# Single_Supply_Logic_Level_Converter.net
KiCad netlist of a schematic drawn in EAGLE
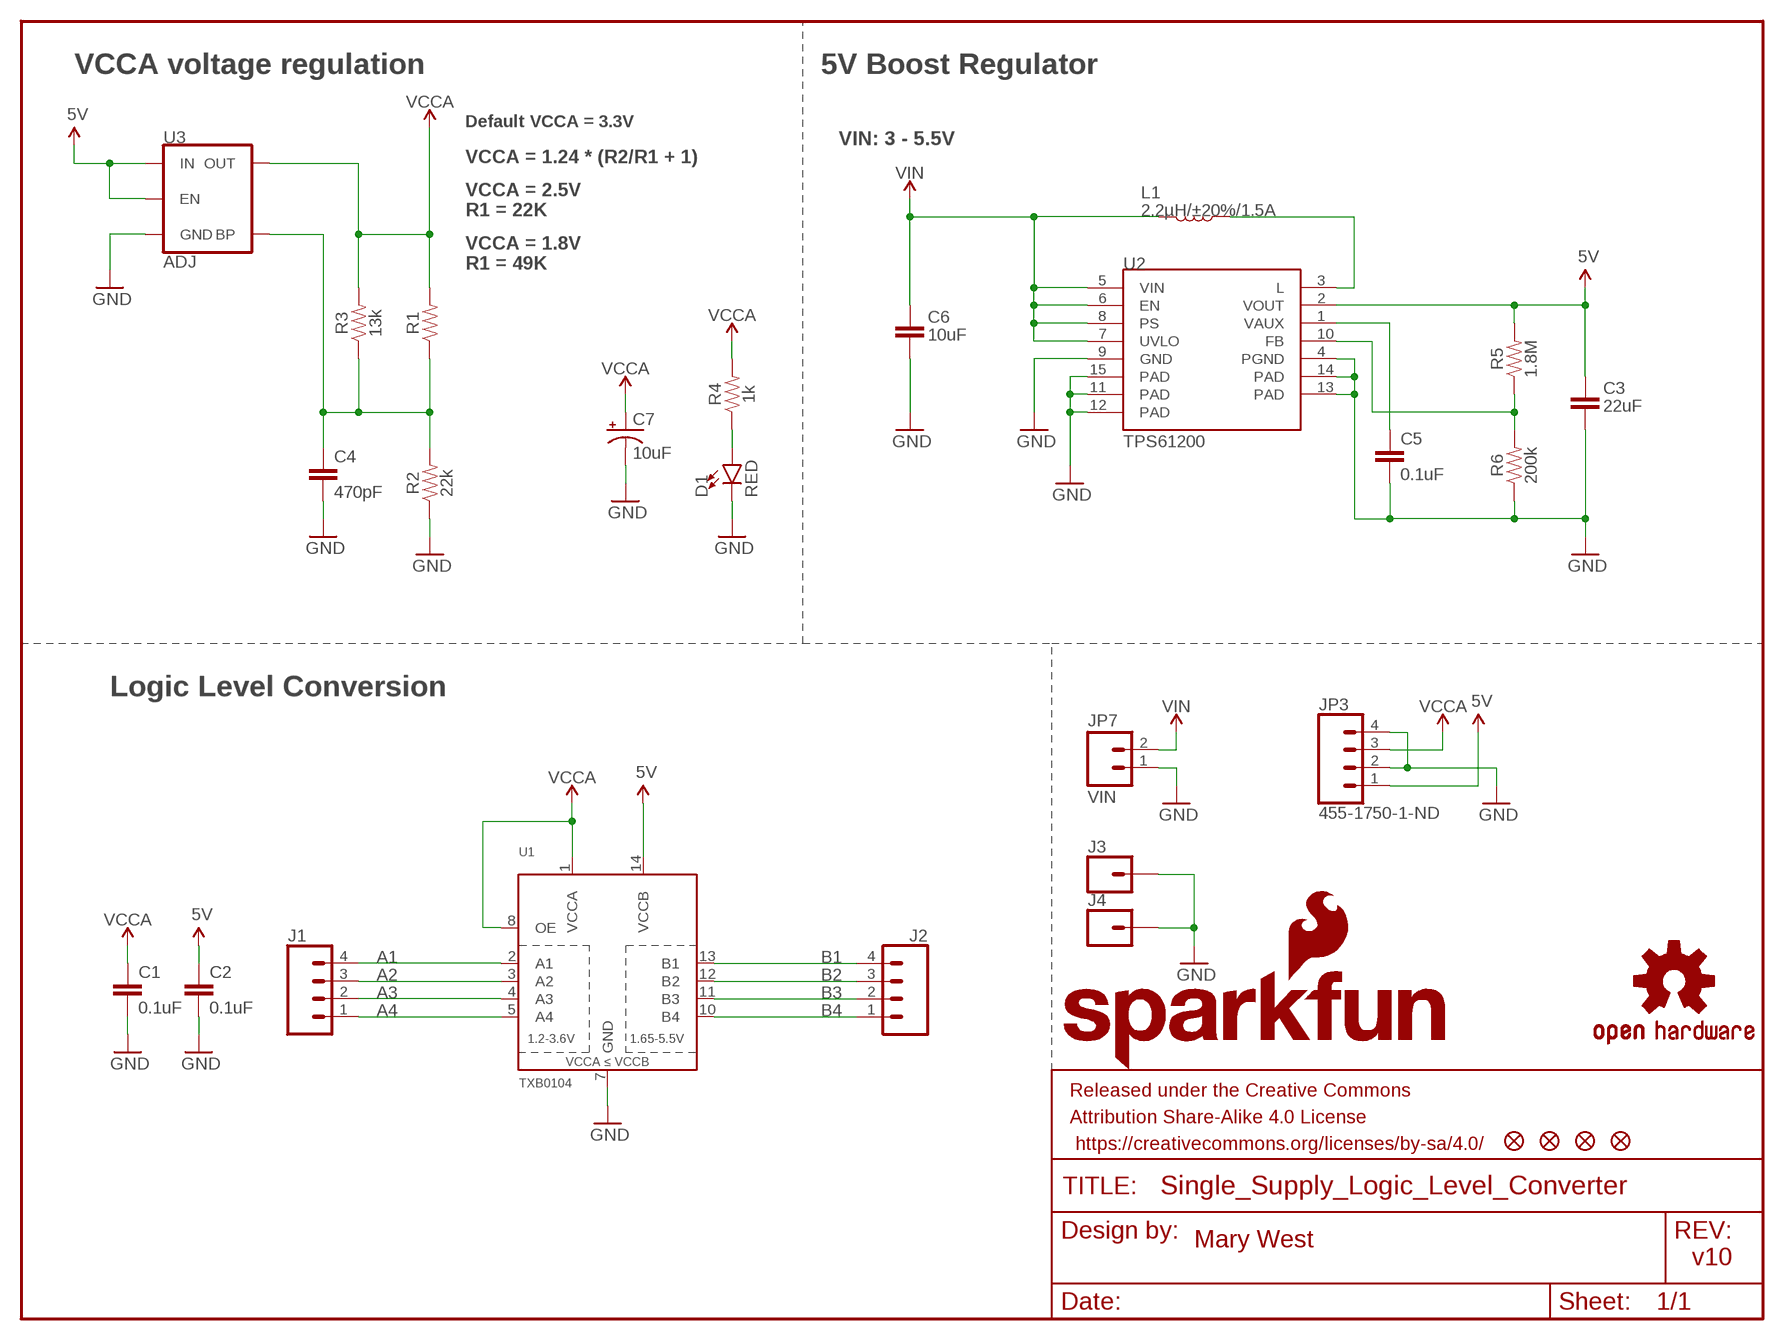
[diagram p0: schematic, sheet 1]

(export (version "E")
  (design (tool "Eeschema 10.0.6"))
  (components
    (comp (ref "C1")
      (value "0.1uF")
      (footprint "eagle-import:0603-CAP")
      (libsource (lib "eagle-import") (part "0.1UF-25V(+80/-20%)(0603)"))
    )
    (comp (ref "C2")
      (value "0.1uF")
      (footprint "eagle-import:0603-CAP")
      (libsource (lib "eagle-import") (part "0.1UF-25V(+80/-20%)(0603)"))
    )
    (comp (ref "C3")
      (value "22uF")
      (footprint "eagle-import:0805")
      (libsource (lib "eagle-import") (part "22UF-0805-6.3V-20%"))
    )
    (comp (ref "C4")
      (value "470pF")
      (footprint "eagle-import:0603")
      (libsource (lib "eagle-import") (part "470PF-0603-50V-5%"))
    )
    (comp (ref "C5")
      (value "0.1uF")
      (footprint "eagle-import:0603")
      (libsource (lib "eagle-import") (part "0.1UF-0603-25V-(+80/-20%)"))
    )
    (comp (ref "C6")
      (value "10uF")
      (footprint "eagle-import:0603")
      (libsource (lib "eagle-import") (part "10UF-0603-6.3V-20%"))
    )
    (comp (ref "C7")
      (value "10uF")
      (footprint "eagle-import:EIA3216")
      (libsource (lib "eagle-import") (part "10UF-POLAR-EIA3216-16V-10%(TANT)"))
    )
    (comp (ref "D1")
      (value "RED")
      (footprint "eagle-import:LED-0603")
      (libsource (lib "eagle-import") (part "LED-RED0603"))
    )
    (comp (ref "FD1")
      (value "FIDUCIALUFIDUCIAL")
      (footprint "eagle-import:FIDUCIAL-MICRO")
      (libsource (lib "eagle-import") (part "FIDUCIALUFIDUCIAL"))
    )
    (comp (ref "FD2")
      (value "FIDUCIALUFIDUCIAL")
      (footprint "eagle-import:FIDUCIAL-MICRO")
      (libsource (lib "eagle-import") (part "FIDUCIALUFIDUCIAL"))
    )
    (comp (ref "FD3")
      (value "FIDUCIALUFIDUCIAL")
      (footprint "eagle-import:FIDUCIAL-MICRO")
      (libsource (lib "eagle-import") (part "FIDUCIALUFIDUCIAL"))
    )
    (comp (ref "FD4")
      (value "FIDUCIALUFIDUCIAL")
      (footprint "eagle-import:FIDUCIAL-MICRO")
      (libsource (lib "eagle-import") (part "FIDUCIALUFIDUCIAL"))
    )
    (comp (ref "FRAME1")
      (value "FRAME-LETTER")
      (footprint "eagle-import:CREATIVE_COMMONS")
      (libsource (lib "eagle-import") (part "FRAME-LETTER"))
    )
    (comp (ref "J1")
      (value "CONN_04")
      (footprint "eagle-import:1X04")
      (libsource (lib "eagle-import") (part "CONN_04"))
    )
    (comp (ref "J2")
      (value "CONN_04")
      (footprint "eagle-import:1X04")
      (libsource (lib "eagle-import") (part "CONN_04"))
    )
    (comp (ref "J3")
      (value "CONN_01")
      (footprint "eagle-import:1X01")
      (libsource (lib "eagle-import") (part "CONN_01"))
    )
    (comp (ref "J4")
      (value "CONN_01")
      (footprint "eagle-import:1X01")
      (libsource (lib "eagle-import") (part "CONN_01"))
    )
    (comp (ref "JP3")
      (value "455-1750-1-ND")
      (footprint "eagle-import:1X04")
      (libsource (lib "eagle-import") (part "CONN_04"))
    )
    (comp (ref "JP7")
      (value "VIN")
      (footprint "eagle-import:1X02")
      (libsource (lib "eagle-import") (part "M02PTH"))
    )
    (comp (ref "L1")
      (value "2.2µH/±20%/1.5A")
      (footprint "eagle-import:INDUCTOR_2.2UH")
      (libsource (lib "eagle-import") (part "INDUCTOR-VLF4012AT-2.2UH"))
    )
    (comp (ref "LOGO1")
      (value "SFE_LOGO_NAME_FLAME.1_INCH")
      (footprint "eagle-import:SFE_LOGO_NAME_FLAME_.1")
      (libsource (lib "eagle-import") (part "SFE_LOGO_NAME_FLAME.1_INCH"))
    )
    (comp (ref "LOGO2")
      (value "OSHW-LOGOS")
      (footprint "eagle-import:OSHW-LOGO-S")
      (libsource (lib "eagle-import") (part "OSHW-LOGOS"))
    )
    (comp (ref "R1")
      (value "RESISTORAXIAL-0.3")
      (footprint "eagle-import:AXIAL-0.3")
      (libsource (lib "eagle-import") (part "RESISTORAXIAL-0.3"))
    )
    (comp (ref "R2")
      (value "22k")
      (footprint "eagle-import:0603")
      (libsource (lib "eagle-import") (part "22KOHM-0603-1/10W-1%"))
    )
    (comp (ref "R3")
      (value "13k")
      (footprint "eagle-import:0603")
      (libsource (lib "eagle-import") (part "13KOHM-0603-1/10W-1%"))
    )
    (comp (ref "R4")
      (value "1k")
      (footprint "eagle-import:0603")
      (libsource (lib "eagle-import") (part "1KOHM-0603-1/10W-1%"))
    )
    (comp (ref "R5")
      (value "1.8M")
      (footprint "eagle-import:0603")
      (libsource (lib "eagle-import") (part "1.8MOHM"))
    )
    (comp (ref "R6")
      (value "200k")
      (footprint "eagle-import:0603")
      (libsource (lib "eagle-import") (part "200KOHM-0603-1/10W-1%"))
    )
    (comp (ref "U1")
      (value "TXB0104")
      (footprint "eagle-import:TSSOP14")
      (libsource (lib "eagle-import") (part "TXB0104PWR"))
    )
    (comp (ref "U2")
      (value "TPS61200")
      (footprint "eagle-import:QFN-10_PAD")
      (libsource (lib "eagle-import") (part "TPS61200"))
    )
    (comp (ref "U3")
      (value "ADJ")
      (footprint "eagle-import:SOT23-5")
      (libsource (lib "eagle-import") (part "V_REG_MIC5205ADJ"))
    )
  )
  (nets
    (net (code "1") (name "/A1") (class "Default")
      (node (ref "J1") (pin "4") (pinfunction "4_4") (pintype "passive"))
      (node (ref "U1") (pin "2") (pinfunction "A1_2") (pintype "bidirectional"))
    )
    (net (code "2") (name "/A2") (class "Default")
      (node (ref "J1") (pin "3") (pinfunction "3_3") (pintype "passive"))
      (node (ref "U1") (pin "3") (pinfunction "A2_3") (pintype "bidirectional"))
    )
    (net (code "3") (name "/A3") (class "Default")
      (node (ref "J1") (pin "2") (pinfunction "2_2") (pintype "passive"))
      (node (ref "U1") (pin "4") (pinfunction "A3_4") (pintype "bidirectional"))
    )
    (net (code "4") (name "/A4") (class "Default")
      (node (ref "J1") (pin "1") (pinfunction "1_1") (pintype "passive"))
      (node (ref "U1") (pin "5") (pinfunction "A4_5") (pintype "bidirectional"))
    )
    (net (code "5") (name "/B1") (class "Default")
      (node (ref "J2") (pin "4") (pinfunction "4_4") (pintype "passive"))
      (node (ref "U1") (pin "13") (pinfunction "B1_13") (pintype "bidirectional"))
    )
    (net (code "6") (name "/B2") (class "Default")
      (node (ref "J2") (pin "3") (pinfunction "3_3") (pintype "passive"))
      (node (ref "U1") (pin "12") (pinfunction "B2_12") (pintype "bidirectional"))
    )
    (net (code "7") (name "/B3") (class "Default")
      (node (ref "J2") (pin "2") (pinfunction "2_2") (pintype "passive"))
      (node (ref "U1") (pin "11") (pinfunction "B3_11") (pintype "bidirectional"))
    )
    (net (code "8") (name "/B4") (class "Default")
      (node (ref "J2") (pin "1") (pinfunction "1_1") (pintype "passive"))
      (node (ref "U1") (pin "10") (pinfunction "B4_10") (pintype "bidirectional"))
    )
    (net (code "9") (name "5V") (class "Default")
      (node (ref "C2") (pin "1") (pinfunction "1_1") (pintype "passive"))
      (node (ref "C3") (pin "1") (pinfunction "1_1") (pintype "passive"))
      (node (ref "JP3") (pin "1") (pinfunction "1_1") (pintype "passive"))
      (node (ref "R5") (pin "2") (pinfunction "2_2") (pintype "passive"))
      (node (ref "U1") (pin "14") (pinfunction "VCCB_14") (pintype "bidirectional"))
      (node (ref "U2") (pin "2") (pinfunction "VOUT_2") (pintype "passive"))
      (node (ref "U3") (pin "1") (pinfunction "IN_1") (pintype "input"))
      (node (ref "U3") (pin "3") (pinfunction "EN_3") (pintype "input"))
    )
    (net (code "10") (name "GND") (class "Default")
      (node (ref "C1") (pin "2") (pinfunction "2_2") (pintype "passive"))
      (node (ref "C2") (pin "2") (pinfunction "2_2") (pintype "passive"))
      (node (ref "C3") (pin "2") (pinfunction "2_2") (pintype "passive"))
      (node (ref "C4") (pin "2") (pinfunction "2_2") (pintype "passive"))
      (node (ref "C5") (pin "2") (pinfunction "2_2") (pintype "passive"))
      (node (ref "C6") (pin "2") (pinfunction "2_2") (pintype "passive"))
      (node (ref "C7") (pin "-") (pinfunction "-_-") (pintype "passive"))
      (node (ref "D1") (pin "C") (pinfunction "C_C") (pintype "passive"))
      (node (ref "J3") (pin "1") (pinfunction "1_1") (pintype "passive"))
      (node (ref "J4") (pin "1") (pinfunction "1_1") (pintype "passive"))
      (node (ref "JP3") (pin "2") (pinfunction "2_2") (pintype "passive"))
      (node (ref "JP3") (pin "4") (pinfunction "4_4") (pintype "passive"))
      (node (ref "JP7") (pin "1") (pinfunction "1_1") (pintype "passive"))
      (node (ref "R2") (pin "1") (pinfunction "1_1") (pintype "passive"))
      (node (ref "R6") (pin "1") (pinfunction "1_1") (pintype "passive"))
      (node (ref "U1") (pin "7") (pinfunction "GND_7") (pintype "bidirectional"))
      (node (ref "U2") (pin "11") (pinfunction "PAD_11") (pintype "power_in"))
      (node (ref "U2") (pin "12") (pinfunction "PAD_12") (pintype "power_in"))
      (node (ref "U2") (pin "13") (pinfunction "PAD_13") (pintype "power_in"))
      (node (ref "U2") (pin "14") (pinfunction "PAD_14") (pintype "power_in"))
      (node (ref "U2") (pin "15") (pinfunction "PAD_15") (pintype "power_in"))
      (node (ref "U2") (pin "4") (pinfunction "PGND_4") (pintype "power_in"))
      (node (ref "U2") (pin "9") (pinfunction "GND_9") (pintype "power_in"))
      (node (ref "U3") (pin "2") (pinfunction "GND_2") (pintype "input"))
    )
    (net (code "11") (name "Net-(D1-PadA)") (class "Default")
      (node (ref "D1") (pin "A") (pinfunction "A_A") (pintype "passive"))
      (node (ref "R4") (pin "1") (pinfunction "1_1") (pintype "passive"))
    )
    (net (code "12") (name "Net-(L1-1)") (class "Default")
      (node (ref "L1") (pin "P$1") (pinfunction "1_P$1") (pintype "passive"))
      (node (ref "U2") (pin "3") (pinfunction "L_3") (pintype "passive"))
    )
    (net (code "13") (name "Net-(R1-1)") (class "Default")
      (node (ref "C4") (pin "1") (pinfunction "1_1") (pintype "passive"))
      (node (ref "R1") (pin "P$1") (pinfunction "1_P$1") (pintype "passive"))
      (node (ref "R2") (pin "2") (pinfunction "2_2") (pintype "passive"))
      (node (ref "R3") (pin "1") (pinfunction "1_1") (pintype "passive"))
      (node (ref "U3") (pin "4") (pinfunction "BP_4") (pintype "input"))
    )
    (net (code "14") (name "Net-(U2-FB)") (class "Default")
      (node (ref "R5") (pin "1") (pinfunction "1_1") (pintype "passive"))
      (node (ref "R6") (pin "2") (pinfunction "2_2") (pintype "passive"))
      (node (ref "U2") (pin "10") (pinfunction "FB_10") (pintype "passive"))
    )
    (net (code "15") (name "Net-(U2-VAUX)") (class "Default")
      (node (ref "C5") (pin "1") (pinfunction "1_1") (pintype "passive"))
      (node (ref "U2") (pin "1") (pinfunction "VAUX_1") (pintype "passive"))
    )
    (net (code "16") (name "VCCA") (class "Default")
      (node (ref "C1") (pin "1") (pinfunction "1_1") (pintype "passive"))
      (node (ref "C7") (pin "+") (pinfunction "+_+") (pintype "passive"))
      (node (ref "JP3") (pin "3") (pinfunction "3_3") (pintype "passive"))
      (node (ref "R1") (pin "P$2") (pinfunction "2_P$2") (pintype "passive"))
      (node (ref "R3") (pin "2") (pinfunction "2_2") (pintype "passive"))
      (node (ref "R4") (pin "2") (pinfunction "2_2") (pintype "passive"))
      (node (ref "U1") (pin "1") (pinfunction "VCCA_1") (pintype "bidirectional"))
      (node (ref "U1") (pin "8") (pinfunction "OE_8") (pintype "bidirectional"))
      (node (ref "U3") (pin "5") (pinfunction "OUT_5") (pintype "passive"))
    )
    (net (code "17") (name "VIN") (class "Default")
      (node (ref "C6") (pin "1") (pinfunction "1_1") (pintype "passive"))
      (node (ref "JP7") (pin "2") (pinfunction "2_2") (pintype "passive"))
      (node (ref "L1") (pin "P$2") (pinfunction "2_P$2") (pintype "passive"))
      (node (ref "U2") (pin "5") (pinfunction "VIN_5") (pintype "power_in"))
      (node (ref "U2") (pin "6") (pinfunction "EN_6") (pintype "input"))
      (node (ref "U2") (pin "7") (pinfunction "UVLO_7") (pintype "passive"))
      (node (ref "U2") (pin "8") (pinfunction "PS_8") (pintype "input"))
    )
  )
)
